# PCB_Slave_Traffic_Light.net
KiCad netlist of a schematic drawn in Altium Designer
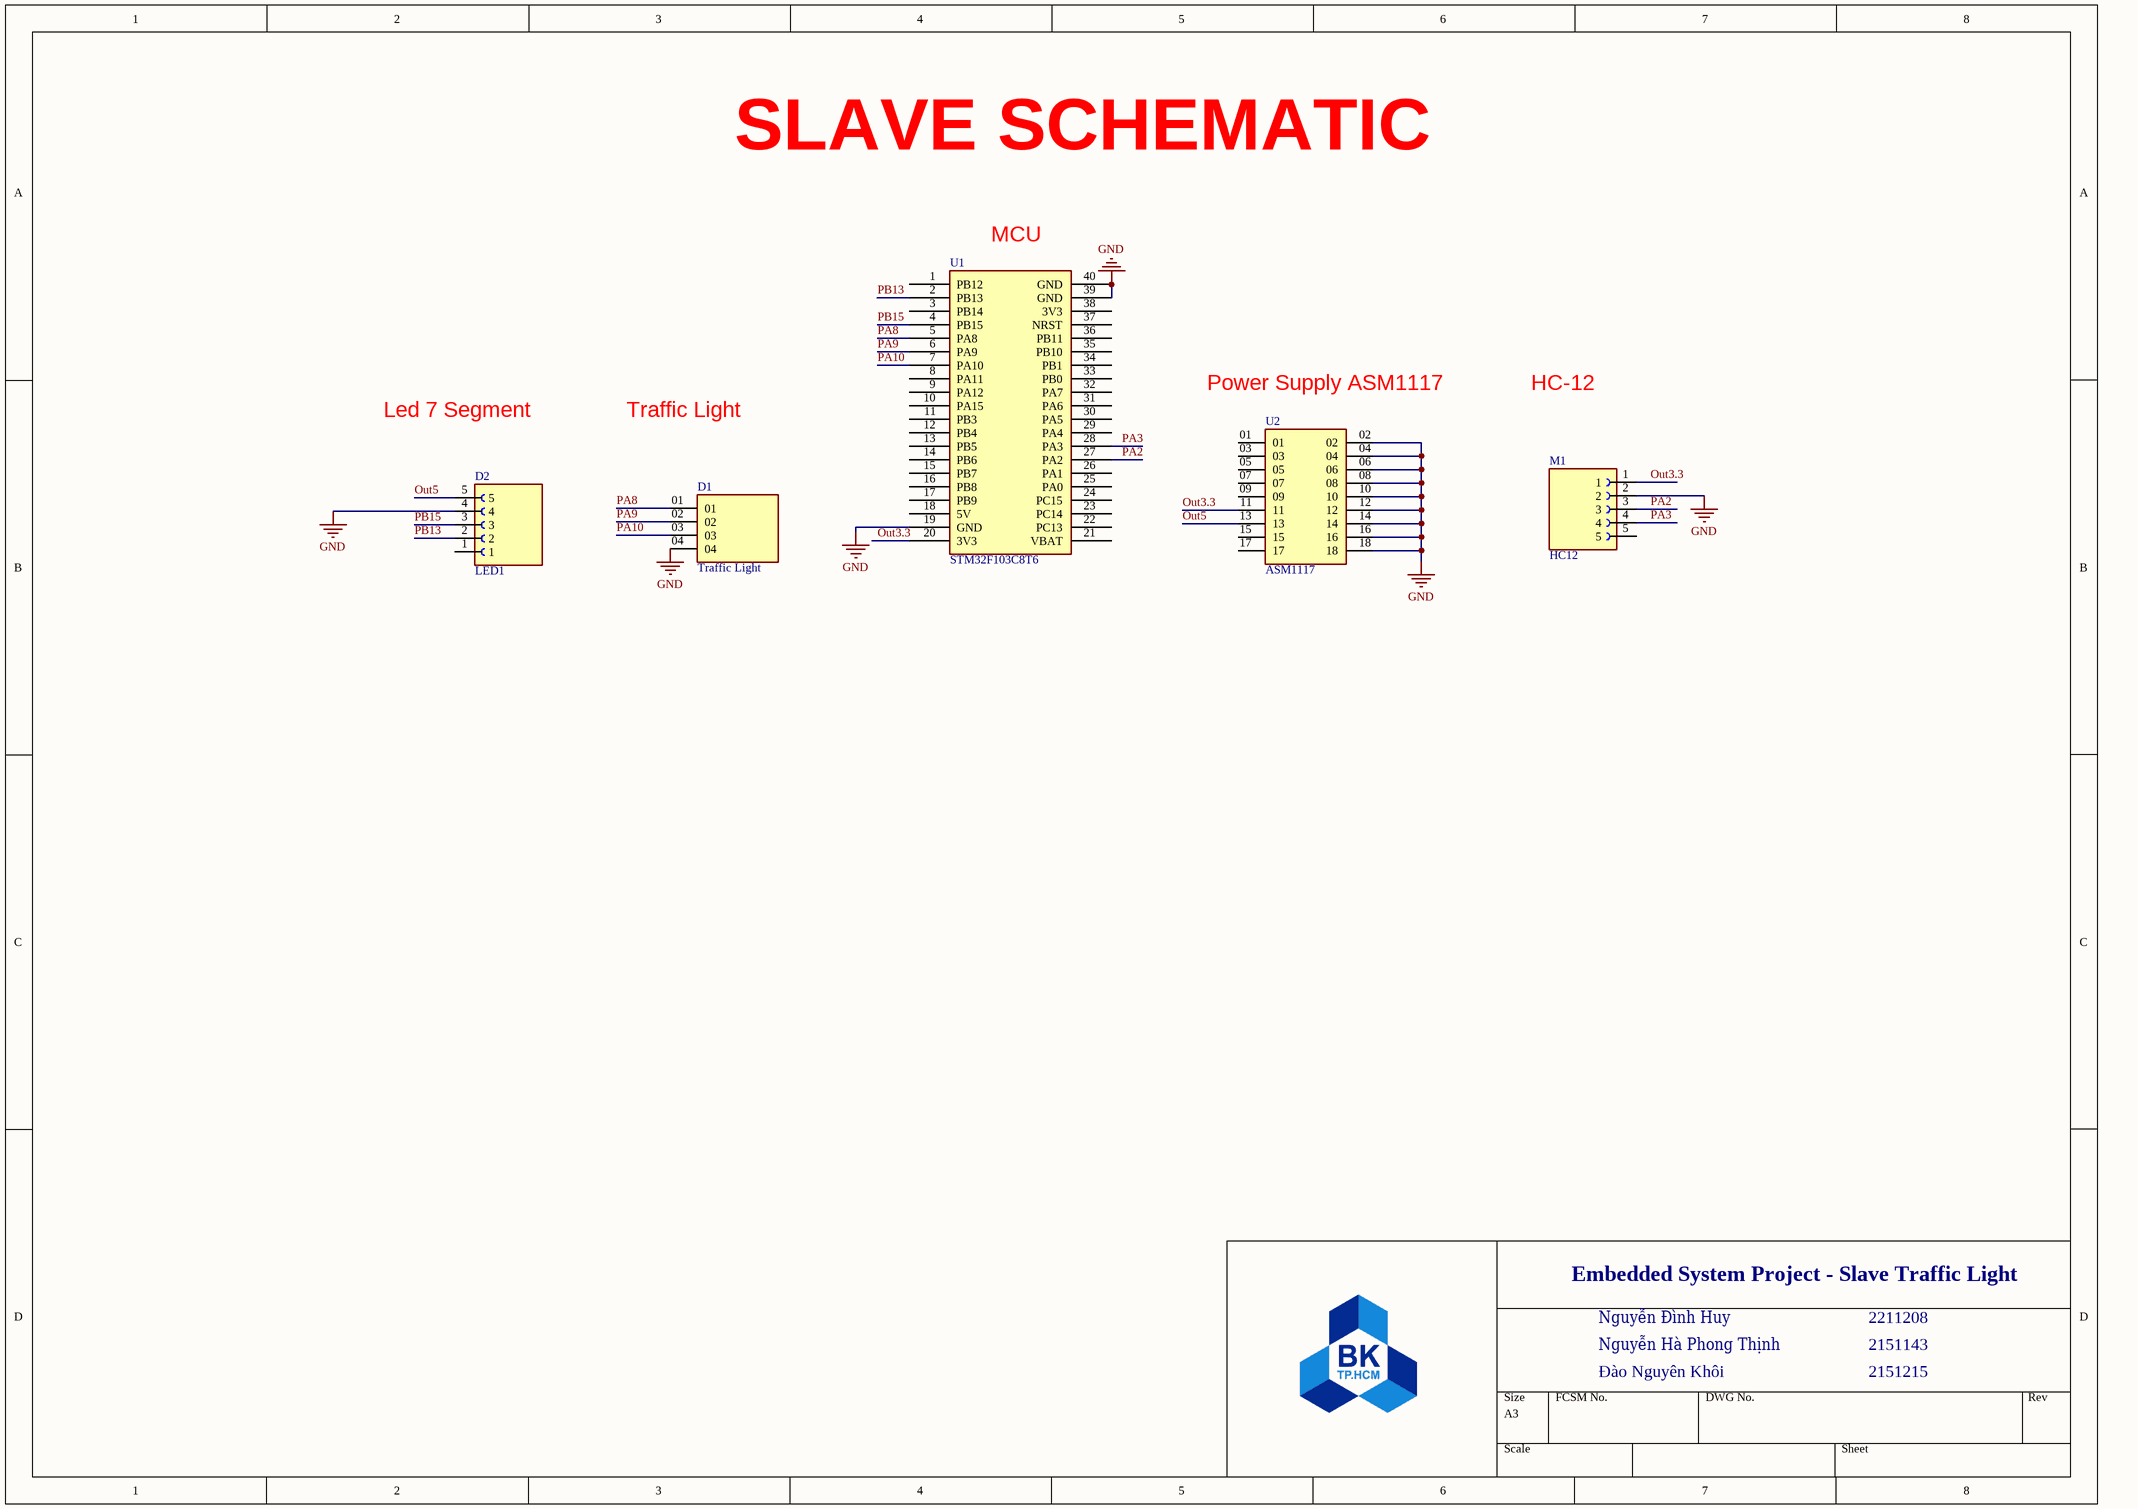
[diagram p0: PCB_Slave_Traffic_Light.SchDoc]

(export (version "E")
  (design (tool "Eeschema 10.0.6"))
  (components
    (comp (ref "D1")
      (value "Traffic Light")
      (footprint "SAMTEC_HTSW-104-23-SM-S")
      (fields (field (name "MF") "Samtec") (field (name "MP") "HTSW10423SMS"))
      (libsource (lib "Header 4x1") (part "HTSW-104-23-SM-S"))
    )
    (comp (ref "D2")
      (value "LED1")
      (footprint "HARWIN_M20-7820546")
      (fields (field (name "MP") "M20-7820546"))
      (libsource (lib "") (part "M20-7820546_1"))
    )
    (comp (ref "M1")
      (value "HC12")
      (footprint "HARWIN_M20-7820546")
      (fields (field (name "MP") "M20-7820546"))
      (libsource (lib "Header 5x1") (part "M20-7820546"))
    )
    (comp (ref "U1")
      (value "STM32F103C8T6")
      (footprint "Stm32 BluePill")
      (description "Designed By @Alixahedi")
      (libsource (lib "Stm32 Blue Pill") (part "BluePill"))
    )
    (comp (ref "U2")
      (value "ASM1117")
      (footprint "SAMTEC_MTSW-109-13-G-D-905")
      (fields (field (name "MP") "MTSW-109-13-G-D-905"))
      (libsource (lib "Header 9x2") (part "MTSW-109-13-G-D-905"))
    )
  )
  (nets
    (net (code "1") (name "/Out3.3") (class "Default")
      (node (ref "M1") (pin "1") (pinfunction "1_1") (pintype "passive"))
      (node (ref "U1") (pin "20") (pinfunction "3V3_20") (pintype "passive"))
      (node (ref "U2") (pin "11") (pinfunction "11_11") (pintype "passive"))
    )
    (net (code "2") (name "/Out5") (class "Default")
      (node (ref "D2") (pin "5") (pinfunction "5_5") (pintype "passive"))
      (node (ref "U2") (pin "13") (pinfunction "13_13") (pintype "passive"))
    )
    (net (code "3") (name "/PA2") (class "Default")
      (node (ref "M1") (pin "3") (pinfunction "3_3") (pintype "passive"))
      (node (ref "U1") (pin "27") (pinfunction "PA2_27") (pintype "passive"))
    )
    (net (code "4") (name "/PA3") (class "Default")
      (node (ref "M1") (pin "4") (pinfunction "4_4") (pintype "passive"))
      (node (ref "U1") (pin "28") (pinfunction "PA3_28") (pintype "passive"))
    )
    (net (code "5") (name "/PA8") (class "Default")
      (node (ref "D1") (pin "01") (pinfunction "01_01") (pintype "passive"))
      (node (ref "U1") (pin "5") (pinfunction "PA8_5") (pintype "passive"))
    )
    (net (code "6") (name "/PA9") (class "Default")
      (node (ref "D1") (pin "02") (pinfunction "02_02") (pintype "passive"))
      (node (ref "U1") (pin "6") (pinfunction "PA9_6") (pintype "passive"))
    )
    (net (code "7") (name "/PA10") (class "Default")
      (node (ref "D1") (pin "03") (pinfunction "03_03") (pintype "passive"))
      (node (ref "U1") (pin "7") (pinfunction "PA10_7") (pintype "passive"))
    )
    (net (code "8") (name "/PB13") (class "Default")
      (node (ref "D2") (pin "2") (pinfunction "2_2") (pintype "passive"))
      (node (ref "U1") (pin "2") (pinfunction "PB13_2") (pintype "passive"))
    )
    (net (code "9") (name "/PB15") (class "Default")
      (node (ref "D2") (pin "3") (pinfunction "3_3") (pintype "passive"))
      (node (ref "U1") (pin "4") (pinfunction "PB15_4") (pintype "passive"))
    )
    (net (code "10") (name "GND") (class "Default")
      (node (ref "D1") (pin "04") (pinfunction "04_04") (pintype "passive"))
      (node (ref "D2") (pin "4") (pinfunction "4_4") (pintype "passive"))
      (node (ref "M1") (pin "2") (pinfunction "2_2") (pintype "passive"))
      (node (ref "U1") (pin "19") (pinfunction "GND_19") (pintype "passive"))
      (node (ref "U1") (pin "39") (pinfunction "GND_39") (pintype "passive"))
      (node (ref "U1") (pin "40") (pinfunction "GND_40") (pintype "passive"))
      (node (ref "U2") (pin "02") (pinfunction "02_02") (pintype "passive"))
      (node (ref "U2") (pin "04") (pinfunction "04_04") (pintype "passive"))
      (node (ref "U2") (pin "06") (pinfunction "06_06") (pintype "passive"))
      (node (ref "U2") (pin "08") (pinfunction "08_08") (pintype "passive"))
      (node (ref "U2") (pin "10") (pinfunction "10_10") (pintype "passive"))
      (node (ref "U2") (pin "12") (pinfunction "12_12") (pintype "passive"))
      (node (ref "U2") (pin "14") (pinfunction "14_14") (pintype "passive"))
      (node (ref "U2") (pin "16") (pinfunction "16_16") (pintype "passive"))
      (node (ref "U2") (pin "18") (pinfunction "18_18") (pintype "passive"))
    )
    (net (code "11") (name "unconnected-(D2-Pad1)") (class "Default")
      (node (ref "D2") (pin "1") (pinfunction "1_1") (pintype "passive"))
    )
    (net (code "12") (name "unconnected-(M1-Pad5)") (class "Default")
      (node (ref "M1") (pin "5") (pinfunction "5_5") (pintype "passive"))
    )
    (net (code "13") (name "unconnected-(U1-3V3-Pad38)") (class "Default")
      (node (ref "U1") (pin "38") (pinfunction "3V3_38") (pintype "passive"))
    )
    (net (code "14") (name "unconnected-(U1-5V-Pad18)") (class "Default")
      (node (ref "U1") (pin "18") (pinfunction "5V_18") (pintype "passive"))
    )
    (net (code "15") (name "unconnected-(U1-NRST-Pad37)") (class "Default")
      (node (ref "U1") (pin "37") (pinfunction "NRST_37") (pintype "passive"))
    )
    (net (code "16") (name "unconnected-(U1-PA0-Pad25)") (class "Default")
      (node (ref "U1") (pin "25") (pinfunction "PA0_25") (pintype "passive"))
    )
    (net (code "17") (name "unconnected-(U1-PA1-Pad26)") (class "Default")
      (node (ref "U1") (pin "26") (pinfunction "PA1_26") (pintype "passive"))
    )
    (net (code "18") (name "unconnected-(U1-PA4-Pad29)") (class "Default")
      (node (ref "U1") (pin "29") (pinfunction "PA4_29") (pintype "passive"))
    )
    (net (code "19") (name "unconnected-(U1-PA5-Pad30)") (class "Default")
      (node (ref "U1") (pin "30") (pinfunction "PA5_30") (pintype "passive"))
    )
    (net (code "20") (name "unconnected-(U1-PA6-Pad31)") (class "Default")
      (node (ref "U1") (pin "31") (pinfunction "PA6_31") (pintype "passive"))
    )
    (net (code "21") (name "unconnected-(U1-PA7-Pad32)") (class "Default")
      (node (ref "U1") (pin "32") (pinfunction "PA7_32") (pintype "passive"))
    )
    (net (code "22") (name "unconnected-(U1-PA11-Pad8)") (class "Default")
      (node (ref "U1") (pin "8") (pinfunction "PA11_8") (pintype "passive"))
    )
    (net (code "23") (name "unconnected-(U1-PA12-Pad9)") (class "Default")
      (node (ref "U1") (pin "9") (pinfunction "PA12_9") (pintype "passive"))
    )
    (net (code "24") (name "unconnected-(U1-PA15-Pad10)") (class "Default")
      (node (ref "U1") (pin "10") (pinfunction "PA15_10") (pintype "passive"))
    )
    (net (code "25") (name "unconnected-(U1-PB0-Pad33)") (class "Default")
      (node (ref "U1") (pin "33") (pinfunction "PB0_33") (pintype "passive"))
    )
    (net (code "26") (name "unconnected-(U1-PB1-Pad34)") (class "Default")
      (node (ref "U1") (pin "34") (pinfunction "PB1_34") (pintype "passive"))
    )
    (net (code "27") (name "unconnected-(U1-PB3-Pad11)") (class "Default")
      (node (ref "U1") (pin "11") (pinfunction "PB3_11") (pintype "passive"))
    )
    (net (code "28") (name "unconnected-(U1-PB4-Pad12)") (class "Default")
      (node (ref "U1") (pin "12") (pinfunction "PB4_12") (pintype "passive"))
    )
    (net (code "29") (name "unconnected-(U1-PB5-Pad13)") (class "Default")
      (node (ref "U1") (pin "13") (pinfunction "PB5_13") (pintype "passive"))
    )
    (net (code "30") (name "unconnected-(U1-PB6-Pad14)") (class "Default")
      (node (ref "U1") (pin "14") (pinfunction "PB6_14") (pintype "passive"))
    )
    (net (code "31") (name "unconnected-(U1-PB7-Pad15)") (class "Default")
      (node (ref "U1") (pin "15") (pinfunction "PB7_15") (pintype "passive"))
    )
    (net (code "32") (name "unconnected-(U1-PB8-Pad16)") (class "Default")
      (node (ref "U1") (pin "16") (pinfunction "PB8_16") (pintype "passive"))
    )
    (net (code "33") (name "unconnected-(U1-PB9-Pad17)") (class "Default")
      (node (ref "U1") (pin "17") (pinfunction "PB9_17") (pintype "passive"))
    )
    (net (code "34") (name "unconnected-(U1-PB10-Pad35)") (class "Default")
      (node (ref "U1") (pin "35") (pinfunction "PB10_35") (pintype "passive"))
    )
    (net (code "35") (name "unconnected-(U1-PB11-Pad36)") (class "Default")
      (node (ref "U1") (pin "36") (pinfunction "PB11_36") (pintype "passive"))
    )
    (net (code "36") (name "unconnected-(U1-PB12-Pad1)") (class "Default")
      (node (ref "U1") (pin "1") (pinfunction "PB12_1") (pintype "passive"))
    )
    (net (code "37") (name "unconnected-(U1-PB14-Pad3)") (class "Default")
      (node (ref "U1") (pin "3") (pinfunction "PB14_3") (pintype "passive"))
    )
    (net (code "38") (name "unconnected-(U1-PC13-Pad22)") (class "Default")
      (node (ref "U1") (pin "22") (pinfunction "PC13_22") (pintype "passive"))
    )
    (net (code "39") (name "unconnected-(U1-PC14-Pad23)") (class "Default")
      (node (ref "U1") (pin "23") (pinfunction "PC14_23") (pintype "passive"))
    )
    (net (code "40") (name "unconnected-(U1-PC15-Pad24)") (class "Default")
      (node (ref "U1") (pin "24") (pinfunction "PC15_24") (pintype "passive"))
    )
    (net (code "41") (name "unconnected-(U1-VBAT-Pad21)") (class "Default")
      (node (ref "U1") (pin "21") (pinfunction "VBAT_21") (pintype "passive"))
    )
    (net (code "42") (name "unconnected-(U2-Pad01)") (class "Default")
      (node (ref "U2") (pin "01") (pinfunction "01_01") (pintype "passive"))
    )
    (net (code "43") (name "unconnected-(U2-Pad03)") (class "Default")
      (node (ref "U2") (pin "03") (pinfunction "03_03") (pintype "passive"))
    )
    (net (code "44") (name "unconnected-(U2-Pad05)") (class "Default")
      (node (ref "U2") (pin "05") (pinfunction "05_05") (pintype "passive"))
    )
    (net (code "45") (name "unconnected-(U2-Pad07)") (class "Default")
      (node (ref "U2") (pin "07") (pinfunction "07_07") (pintype "passive"))
    )
    (net (code "46") (name "unconnected-(U2-Pad09)") (class "Default")
      (node (ref "U2") (pin "09") (pinfunction "09_09") (pintype "passive"))
    )
    (net (code "47") (name "unconnected-(U2-Pad15)") (class "Default")
      (node (ref "U2") (pin "15") (pinfunction "15_15") (pintype "passive"))
    )
    (net (code "48") (name "unconnected-(U2-Pad17)") (class "Default")
      (node (ref "U2") (pin "17") (pinfunction "17_17") (pintype "passive"))
    )
  )
)
